# PoRN.net
KiCad netlist of a schematic drawn in EAGLE
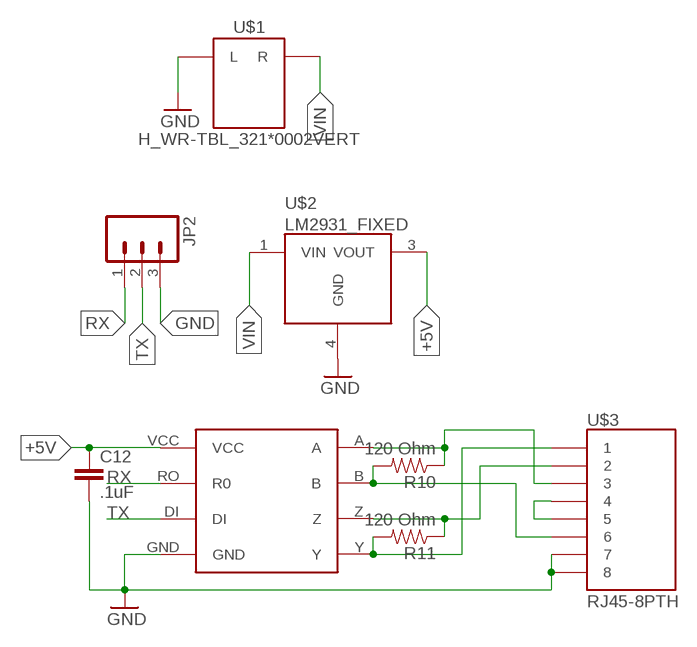
[diagram p0: schematic, sheet 1]

(export (version "E")
  (design (tool "Eeschema 10.0.6"))
  (components
    (comp (ref "C12")
      (value ".1uF")
      (footprint "eagle-import:1206")
      (libsource (lib "eagle-import") (part "CAP1206"))
    )
    (comp (ref "JP2")
      (value "M03PTH")
      (footprint "eagle-import:1X03")
      (libsource (lib "eagle-import") (part "M03PTH"))
    )
    (comp (ref "R10")
      (value "120 Ohm")
      (footprint "eagle-import:1206")
      (libsource (lib "eagle-import") (part "RESISTOR1206"))
    )
    (comp (ref "R11")
      (value "120 Ohm")
      (footprint "eagle-import:1206")
      (libsource (lib "eagle-import") (part "RESISTOR1206"))
    )
    (comp (ref "U$1")
      (value "H_WR-TBL_321*0002VERT")
      (footprint "eagle-import:691321100002")
      (libsource (lib "eagle-import") (part "H_WR-TBL_3210002VERT"))
    )
    (comp (ref "U$2")
      (value "LM2931_FIXED")
      (footprint "eagle-import:DPAK")
      (libsource (lib "eagle-import") (part "LM2931_FIXED"))
    )
    (comp (ref "U$3")
      (value "RJ45-8PTH")
      (footprint "eagle-import:RJ45-8")
      (libsource (lib "eagle-import") (part "RJ45-8PTH"))
    )
    (comp (ref "U$4")
      (value "MAX3077")
      (footprint "eagle-import:MAX3070E")
      (libsource (lib "eagle-import") (part "MAX3077"))
    )
  )
  (nets
    (net (code "1") (name "+5V") (class "Default")
      (node (ref "C12") (pin "1") (pinfunction "1_1") (pintype "passive"))
      (node (ref "U$2") (pin "3") (pinfunction "VOUT_3") (pintype "bidirectional"))
      (node (ref "U$3") (pin "4") (pinfunction "4_4") (pintype "bidirectional"))
      (node (ref "U$3") (pin "5") (pinfunction "5_5") (pintype "bidirectional"))
      (node (ref "U$4") (pin "VCC") (pinfunction "VCC_VCC") (pintype "bidirectional"))
    )
    (net (code "2") (name "GND") (class "Default")
      (node (ref "C12") (pin "2") (pinfunction "2_2") (pintype "passive"))
      (node (ref "JP2") (pin "3") (pinfunction "3_3") (pintype "passive"))
      (node (ref "U$1") (pin "L") (pinfunction "L_L") (pintype "bidirectional"))
      (node (ref "U$2") (pin "4") (pinfunction "GND_4") (pintype "bidirectional"))
      (node (ref "U$3") (pin "7") (pinfunction "7_7") (pintype "bidirectional"))
      (node (ref "U$3") (pin "8") (pinfunction "8_8") (pintype "bidirectional"))
      (node (ref "U$4") (pin "GND") (pinfunction "GND_GND") (pintype "bidirectional"))
    )
    (net (code "3") (name "Net-(R10-Pad1)") (class "Default")
      (node (ref "R10") (pin "1") (pinfunction "1_1") (pintype "passive"))
      (node (ref "U$3") (pin "3") (pinfunction "3_3") (pintype "bidirectional"))
      (node (ref "U$4") (pin "A") (pinfunction "A_A") (pintype "bidirectional"))
    )
    (net (code "4") (name "Net-(R10-Pad2)") (class "Default")
      (node (ref "R10") (pin "2") (pinfunction "2_2") (pintype "passive"))
      (node (ref "U$3") (pin "6") (pinfunction "6_6") (pintype "bidirectional"))
      (node (ref "U$4") (pin "B") (pinfunction "B_B") (pintype "bidirectional"))
    )
    (net (code "5") (name "Net-(R11-Pad1)") (class "Default")
      (node (ref "R11") (pin "1") (pinfunction "1_1") (pintype "passive"))
      (node (ref "U$3") (pin "2") (pinfunction "2_2") (pintype "bidirectional"))
      (node (ref "U$4") (pin "Z") (pinfunction "Z_Z") (pintype "bidirectional"))
    )
    (net (code "6") (name "Net-(R11-Pad2)") (class "Default")
      (node (ref "R11") (pin "2") (pinfunction "2_2") (pintype "passive"))
      (node (ref "U$3") (pin "1") (pinfunction "1_1") (pintype "bidirectional"))
      (node (ref "U$4") (pin "Y") (pinfunction "Y_Y") (pintype "bidirectional"))
    )
    (net (code "7") (name "RX") (class "Default")
      (node (ref "JP2") (pin "1") (pinfunction "1_1") (pintype "passive"))
      (node (ref "U$4") (pin "RO") (pinfunction "R0_RO") (pintype "bidirectional"))
    )
    (net (code "8") (name "TX") (class "Default")
      (node (ref "JP2") (pin "2") (pinfunction "2_2") (pintype "passive"))
      (node (ref "U$4") (pin "DI") (pinfunction "DI_DI") (pintype "bidirectional"))
    )
    (net (code "9") (name "VIN") (class "Default")
      (node (ref "U$1") (pin "R") (pinfunction "R_R") (pintype "bidirectional"))
      (node (ref "U$2") (pin "1") (pinfunction "VIN_1") (pintype "bidirectional"))
    )
  )
)
